# VL53L1X-SATEL.net
KiCad netlist of a schematic drawn in Altium Designer
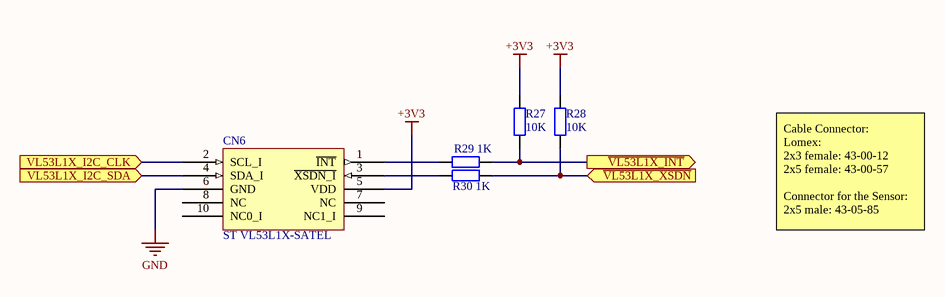
[diagram p0: VL53L1X-SATEL.SchDoc]

(export (version "E")
  (design (tool "Eeschema 10.0.6"))
  (components
    (comp (ref "CN6")
      (value "ST VL53L1X-SATEL")
      (footprint "FP_DISTANCE_SENSOR")
      (description "53L1-SATEL-I1 satellite board for ranging sensor (max distance 4m)")
      (libsource (lib "LKBulls2023") (part "ST_53L1-SATEL-I1"))
    )
    (comp (ref "R27")
      (value "10K")
      (footprint "FP_0805_RES")
      (description "Resistor")
      (fields (field (name "TOLERANCE") "5%") (field (name "POWER") "0.125W"))
      (libsource (lib "LKBulls2023") (part "RES"))
    )
    (comp (ref "R28")
      (value "10K")
      (footprint "FP_0805_RES")
      (description "Resistor")
      (fields (field (name "TOLERANCE") "5%") (field (name "POWER") "0.125W"))
      (libsource (lib "LKBulls2023") (part "RES"))
    )
    (comp (ref "R29")
      (value "1K")
      (footprint "FP_0805_RES")
      (description "Resistor")
      (fields (field (name "TOLERANCE") "5%") (field (name "POWER") "0.125W"))
      (libsource (lib "") (part "RES_1"))
    )
    (comp (ref "R30")
      (value "1K")
      (footprint "FP_0805_RES")
      (description "Resistor")
      (fields (field (name "TOLERANCE") "5%") (field (name "POWER") "0.125W"))
      (libsource (lib "") (part "RES_1"))
    )
  )
  (nets
    (net (code "1") (name "+3V3") (class "Default")
      (node (ref "CN6") (pin "5") (pinfunction "VDD_5") (pintype "power_in"))
      (node (ref "R27") (pin "1") (pinfunction "1_1") (pintype "passive"))
      (node (ref "R28") (pin "1") (pinfunction "1_1") (pintype "passive"))
    )
    (net (code "2") (name "/VL53L1X_I2C_CLK") (class "Default")
      (node (ref "CN6") (pin "2") (pinfunction "SCL_I_2") (pintype "input"))
    )
    (net (code "3") (name "/VL53L1X_I2C_SDA") (class "Default")
      (node (ref "CN6") (pin "4") (pinfunction "SDA_I_4") (pintype "input"))
    )
    (net (code "4") (name "/~{VL53L1X_INT}") (class "Default")
      (node (ref "R27") (pin "2") (pinfunction "2_2") (pintype "passive"))
      (node (ref "R29") (pin "2") (pinfunction "2_2") (pintype "passive"))
    )
    (net (code "5") (name "/~{VL53L1X_XSDN}") (class "Default")
      (node (ref "R28") (pin "2") (pinfunction "2_2") (pintype "passive"))
      (node (ref "R30") (pin "2") (pinfunction "2_2") (pintype "passive"))
    )
    (net (code "6") (name "GND") (class "Default")
      (node (ref "CN6") (pin "6") (pinfunction "GND_6") (pintype "passive"))
    )
    (net (code "7") (name "Net-(CN6-~{INT})") (class "Default")
      (node (ref "CN6") (pin "1") (pinfunction "~{INT}_1") (pintype "output"))
      (node (ref "R29") (pin "1") (pinfunction "1_1") (pintype "passive"))
    )
    (net (code "8") (name "Net-(CN6-~{XSDN_I})") (class "Default")
      (node (ref "CN6") (pin "3") (pinfunction "~{XSDN_I}_3") (pintype "input"))
      (node (ref "R30") (pin "1") (pinfunction "1_1") (pintype "passive"))
    )
    (net (code "9") (name "unconnected-(CN6-NC-Pad7)") (class "Default")
      (node (ref "CN6") (pin "7") (pinfunction "NC_7") (pintype "passive"))
    )
    (net (code "10") (name "unconnected-(CN6-NC-Pad8)") (class "Default")
      (node (ref "CN6") (pin "8") (pinfunction "NC_8") (pintype "passive"))
    )
    (net (code "11") (name "unconnected-(CN6-NC0_I-Pad10)") (class "Default")
      (node (ref "CN6") (pin "10") (pinfunction "NC0_I_10") (pintype "passive"))
    )
    (net (code "12") (name "unconnected-(CN6-NC1_I-Pad9)") (class "Default")
      (node (ref "CN6") (pin "9") (pinfunction "NC1_I_9") (pintype "passive"))
    )
  )
)
